# Strain_In.net
KiCad netlist of a schematic drawn in Altium Designer
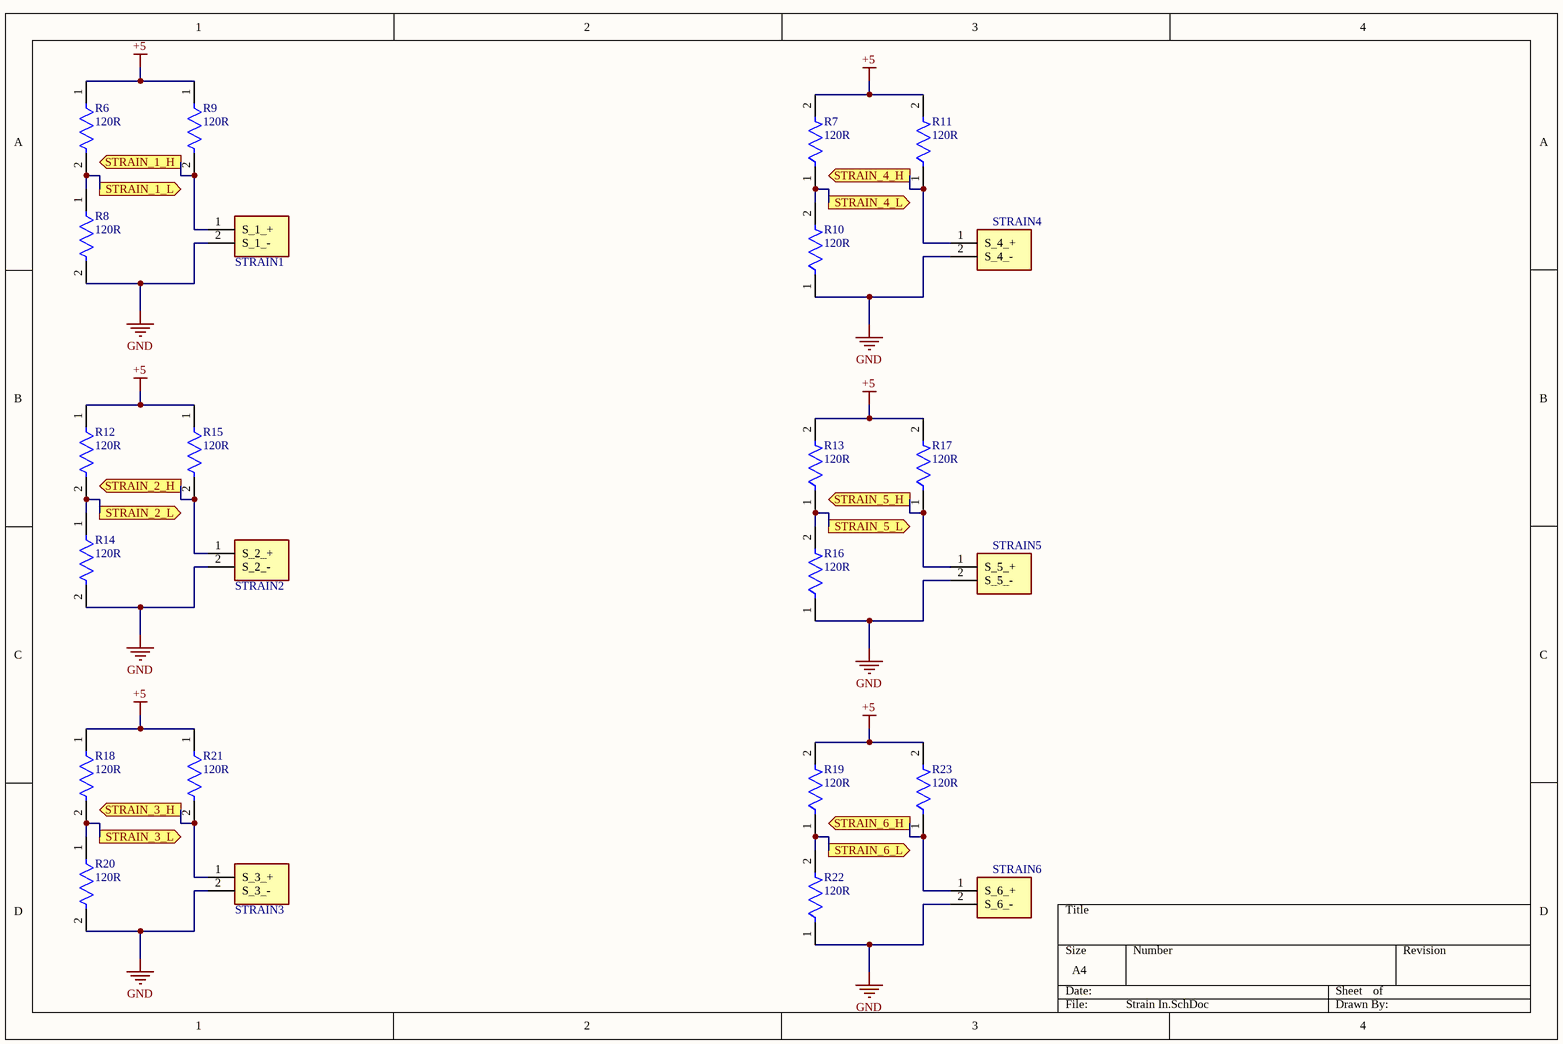
[diagram p0: Strain In.SchDoc]

(export (version "E")
  (design (tool "Eeschema 10.0.6"))
  (components
    (comp (ref "R6")
      (value "120R")
      (footprint "FP-CRCW1206-e3-MFG")
      (description "RES Thick Film, 120Ω, 1%, 0.25W, 100ppm/°C, 1206")
      (fields (field (name "TOLERANCE") "1%"))
      (libsource (lib "Altium Content Vault") (part "1029c3af85768c4190bb7ad29bc67b5"))
    )
    (comp (ref "R7")
      (value "120R")
      (footprint "FP-CRCW1206-e3-MFG")
      (description "RES Thick Film, 120Ω, 1%, 0.25W, 100ppm/°C, 1206")
      (fields (field (name "TOLERANCE") "1%"))
      (libsource (lib "Altium Content Vault") (part "1029c3af85768c4190bb7ad29bc67b5"))
    )
    (comp (ref "R8")
      (value "120R")
      (footprint "FP-CRCW1206-e3-MFG")
      (description "RES Thick Film, 120Ω, 1%, 0.25W, 100ppm/°C, 1206")
      (fields (field (name "TOLERANCE") "1%"))
      (libsource (lib "Altium Content Vault") (part "1029c3af85768c4190bb7ad29bc67b5"))
    )
    (comp (ref "R9")
      (value "120R")
      (footprint "FP-CRCW1206-e3-MFG")
      (description "RES Thick Film, 120Ω, 1%, 0.25W, 100ppm/°C, 1206")
      (fields (field (name "TOLERANCE") "1%"))
      (libsource (lib "Altium Content Vault") (part "1029c3af85768c4190bb7ad29bc67b5"))
    )
    (comp (ref "R10")
      (value "120R")
      (footprint "FP-CRCW1206-e3-MFG")
      (description "RES Thick Film, 120Ω, 1%, 0.25W, 100ppm/°C, 1206")
      (fields (field (name "TOLERANCE") "1%"))
      (libsource (lib "Altium Content Vault") (part "1029c3af85768c4190bb7ad29bc67b5"))
    )
    (comp (ref "R11")
      (value "120R")
      (footprint "FP-CRCW1206-e3-MFG")
      (description "RES Thick Film, 120Ω, 1%, 0.25W, 100ppm/°C, 1206")
      (fields (field (name "TOLERANCE") "1%"))
      (libsource (lib "Altium Content Vault") (part "1029c3af85768c4190bb7ad29bc67b5"))
    )
    (comp (ref "R12")
      (value "120R")
      (footprint "FP-CRCW1206-e3-MFG")
      (description "RES Thick Film, 120Ω, 1%, 0.25W, 100ppm/°C, 1206")
      (fields (field (name "TOLERANCE") "1%"))
      (libsource (lib "Altium Content Vault") (part "1029c3af85768c4190bb7ad29bc67b5"))
    )
    (comp (ref "R13")
      (value "120R")
      (footprint "FP-CRCW1206-e3-MFG")
      (description "RES Thick Film, 120Ω, 1%, 0.25W, 100ppm/°C, 1206")
      (fields (field (name "TOLERANCE") "1%"))
      (libsource (lib "Altium Content Vault") (part "1029c3af85768c4190bb7ad29bc67b5"))
    )
    (comp (ref "R14")
      (value "120R")
      (footprint "FP-CRCW1206-e3-MFG")
      (description "RES Thick Film, 120Ω, 1%, 0.25W, 100ppm/°C, 1206")
      (fields (field (name "TOLERANCE") "1%"))
      (libsource (lib "Altium Content Vault") (part "1029c3af85768c4190bb7ad29bc67b5"))
    )
    (comp (ref "R15")
      (value "120R")
      (footprint "FP-CRCW1206-e3-MFG")
      (description "RES Thick Film, 120Ω, 1%, 0.25W, 100ppm/°C, 1206")
      (fields (field (name "TOLERANCE") "1%"))
      (libsource (lib "Altium Content Vault") (part "1029c3af85768c4190bb7ad29bc67b5"))
    )
    (comp (ref "R16")
      (value "120R")
      (footprint "FP-CRCW1206-e3-MFG")
      (description "RES Thick Film, 120Ω, 1%, 0.25W, 100ppm/°C, 1206")
      (fields (field (name "TOLERANCE") "1%"))
      (libsource (lib "Altium Content Vault") (part "1029c3af85768c4190bb7ad29bc67b5"))
    )
    (comp (ref "R17")
      (value "120R")
      (footprint "FP-CRCW1206-e3-MFG")
      (description "RES Thick Film, 120Ω, 1%, 0.25W, 100ppm/°C, 1206")
      (fields (field (name "TOLERANCE") "1%"))
      (libsource (lib "Altium Content Vault") (part "1029c3af85768c4190bb7ad29bc67b5"))
    )
    (comp (ref "R18")
      (value "120R")
      (footprint "FP-CRCW1206-e3-MFG")
      (description "RES Thick Film, 120Ω, 1%, 0.25W, 100ppm/°C, 1206")
      (fields (field (name "TOLERANCE") "1%"))
      (libsource (lib "Altium Content Vault") (part "1029c3af85768c4190bb7ad29bc67b5"))
    )
    (comp (ref "R19")
      (value "120R")
      (footprint "FP-CRCW1206-e3-MFG")
      (description "RES Thick Film, 120Ω, 1%, 0.25W, 100ppm/°C, 1206")
      (fields (field (name "TOLERANCE") "1%"))
      (libsource (lib "Altium Content Vault") (part "1029c3af85768c4190bb7ad29bc67b5"))
    )
    (comp (ref "R20")
      (value "120R")
      (footprint "FP-CRCW1206-e3-MFG")
      (description "RES Thick Film, 120Ω, 1%, 0.25W, 100ppm/°C, 1206")
      (fields (field (name "TOLERANCE") "1%"))
      (libsource (lib "Altium Content Vault") (part "1029c3af85768c4190bb7ad29bc67b5"))
    )
    (comp (ref "R21")
      (value "120R")
      (footprint "FP-CRCW1206-e3-MFG")
      (description "RES Thick Film, 120Ω, 1%, 0.25W, 100ppm/°C, 1206")
      (fields (field (name "TOLERANCE") "1%"))
      (libsource (lib "Altium Content Vault") (part "1029c3af85768c4190bb7ad29bc67b5"))
    )
    (comp (ref "R22")
      (value "120R")
      (footprint "FP-CRCW1206-e3-MFG")
      (description "RES Thick Film, 120Ω, 1%, 0.25W, 100ppm/°C, 1206")
      (fields (field (name "TOLERANCE") "1%"))
      (libsource (lib "Altium Content Vault") (part "1029c3af85768c4190bb7ad29bc67b5"))
    )
    (comp (ref "R23")
      (value "120R")
      (footprint "FP-CRCW1206-e3-MFG")
      (description "RES Thick Film, 120Ω, 1%, 0.25W, 100ppm/°C, 1206")
      (fields (field (name "TOLERANCE") "1%"))
      (libsource (lib "Altium Content Vault") (part "1029c3af85768c4190bb7ad29bc67b5"))
    )
    (comp (ref "STRAIN1")
      (value "171971-0002")
      (footprint "SamacSys:SHDR2W65P0X254_1X2_738X510X1216P")
      (description "Connector")
      (fields (field (name "MOUSER2 PART NUMBER") "538-171971-0002"))
      (libsource (lib "SamacSys") (part "171971-0002"))
    )
    (comp (ref "STRAIN2")
      (value "171971-0002")
      (footprint "SamacSys:SHDR2W65P0X254_1X2_738X510X1216P")
      (description "Connector")
      (fields (field (name "MOUSER2 PART NUMBER") "538-171971-0002"))
      (libsource (lib "SamacSys") (part "171971-0002"))
    )
    (comp (ref "STRAIN3")
      (value "171971-0002")
      (footprint "SamacSys:SHDR2W65P0X254_1X2_738X510X1216P")
      (description "Connector")
      (fields (field (name "MOUSER2 PART NUMBER") "538-171971-0002"))
      (libsource (lib "SamacSys") (part "171971-0002"))
    )
    (comp (ref "STRAIN4")
      (value "171971-0002")
      (footprint "SamacSys:SHDR2W65P0X254_1X2_738X510X1216P")
      (description "Connector")
      (fields (field (name "MOUSER2 PART NUMBER") "538-171971-0002"))
      (libsource (lib "SamacSys") (part "171971-0002"))
    )
    (comp (ref "STRAIN5")
      (value "171971-0002")
      (footprint "SamacSys:SHDR2W65P0X254_1X2_738X510X1216P")
      (description "Connector")
      (fields (field (name "MOUSER2 PART NUMBER") "538-171971-0002"))
      (libsource (lib "SamacSys") (part "171971-0002"))
    )
    (comp (ref "STRAIN6")
      (value "171971-0002")
      (footprint "SamacSys:SHDR2W65P0X254_1X2_738X510X1216P")
      (description "Connector")
      (fields (field (name "MOUSER2 PART NUMBER") "538-171971-0002"))
      (libsource (lib "SamacSys") (part "171971-0002"))
    )
  )
  (nets
    (net (code "1") (name "+5") (class "Default")
      (node (ref "R11") (pin "2") (pinfunction "2_2") (pintype "passive"))
      (node (ref "R12") (pin "1") (pinfunction "1_1") (pintype "passive"))
      (node (ref "R13") (pin "2") (pinfunction "2_2") (pintype "passive"))
      (node (ref "R15") (pin "1") (pinfunction "1_1") (pintype "passive"))
      (node (ref "R17") (pin "2") (pinfunction "2_2") (pintype "passive"))
      (node (ref "R18") (pin "1") (pinfunction "1_1") (pintype "passive"))
      (node (ref "R19") (pin "2") (pinfunction "2_2") (pintype "passive"))
      (node (ref "R21") (pin "1") (pinfunction "1_1") (pintype "passive"))
      (node (ref "R23") (pin "2") (pinfunction "2_2") (pintype "passive"))
      (node (ref "R6") (pin "1") (pinfunction "1_1") (pintype "passive"))
      (node (ref "R7") (pin "2") (pinfunction "2_2") (pintype "passive"))
      (node (ref "R9") (pin "1") (pinfunction "1_1") (pintype "passive"))
    )
    (net (code "2") (name "/STRAIN_1_H") (class "Default")
      (node (ref "R9") (pin "2") (pinfunction "2_2") (pintype "passive"))
      (node (ref "STRAIN1") (pin "1") (pinfunction "S_1_+_1") (pintype "passive"))
    )
    (net (code "3") (name "/STRAIN_1_L") (class "Default")
      (node (ref "R6") (pin "2") (pinfunction "2_2") (pintype "passive"))
      (node (ref "R8") (pin "1") (pinfunction "1_1") (pintype "passive"))
    )
    (net (code "4") (name "/STRAIN_2_H") (class "Default")
      (node (ref "R15") (pin "2") (pinfunction "2_2") (pintype "passive"))
      (node (ref "STRAIN2") (pin "1") (pinfunction "S_1_+_1") (pintype "passive"))
    )
    (net (code "5") (name "/STRAIN_2_L") (class "Default")
      (node (ref "R12") (pin "2") (pinfunction "2_2") (pintype "passive"))
      (node (ref "R14") (pin "1") (pinfunction "1_1") (pintype "passive"))
    )
    (net (code "6") (name "/STRAIN_3_H") (class "Default")
      (node (ref "R21") (pin "2") (pinfunction "2_2") (pintype "passive"))
      (node (ref "STRAIN3") (pin "1") (pinfunction "S_1_+_1") (pintype "passive"))
    )
    (net (code "7") (name "/STRAIN_3_L") (class "Default")
      (node (ref "R18") (pin "2") (pinfunction "2_2") (pintype "passive"))
      (node (ref "R20") (pin "1") (pinfunction "1_1") (pintype "passive"))
    )
    (net (code "8") (name "/STRAIN_4_H") (class "Default")
      (node (ref "R11") (pin "1") (pinfunction "1_1") (pintype "passive"))
      (node (ref "STRAIN4") (pin "1") (pinfunction "S_1_+_1") (pintype "passive"))
    )
    (net (code "9") (name "/STRAIN_4_L") (class "Default")
      (node (ref "R10") (pin "2") (pinfunction "2_2") (pintype "passive"))
      (node (ref "R7") (pin "1") (pinfunction "1_1") (pintype "passive"))
    )
    (net (code "10") (name "/STRAIN_5_H") (class "Default")
      (node (ref "R17") (pin "1") (pinfunction "1_1") (pintype "passive"))
      (node (ref "STRAIN5") (pin "1") (pinfunction "S_1_+_1") (pintype "passive"))
    )
    (net (code "11") (name "/STRAIN_5_L") (class "Default")
      (node (ref "R13") (pin "1") (pinfunction "1_1") (pintype "passive"))
      (node (ref "R16") (pin "2") (pinfunction "2_2") (pintype "passive"))
    )
    (net (code "12") (name "/STRAIN_6_H") (class "Default")
      (node (ref "R23") (pin "1") (pinfunction "1_1") (pintype "passive"))
      (node (ref "STRAIN6") (pin "1") (pinfunction "S_1_+_1") (pintype "passive"))
    )
    (net (code "13") (name "/STRAIN_6_L") (class "Default")
      (node (ref "R19") (pin "1") (pinfunction "1_1") (pintype "passive"))
      (node (ref "R22") (pin "2") (pinfunction "2_2") (pintype "passive"))
    )
    (net (code "14") (name "GND") (class "Default")
      (node (ref "R10") (pin "1") (pinfunction "1_1") (pintype "passive"))
      (node (ref "R14") (pin "2") (pinfunction "2_2") (pintype "passive"))
      (node (ref "R16") (pin "1") (pinfunction "1_1") (pintype "passive"))
      (node (ref "R20") (pin "2") (pinfunction "2_2") (pintype "passive"))
      (node (ref "R22") (pin "1") (pinfunction "1_1") (pintype "passive"))
      (node (ref "R8") (pin "2") (pinfunction "2_2") (pintype "passive"))
      (node (ref "STRAIN1") (pin "2") (pinfunction "S_1_-_2") (pintype "passive"))
      (node (ref "STRAIN2") (pin "2") (pinfunction "S_1_-_2") (pintype "passive"))
      (node (ref "STRAIN3") (pin "2") (pinfunction "S_1_-_2") (pintype "passive"))
      (node (ref "STRAIN4") (pin "2") (pinfunction "S_1_-_2") (pintype "passive"))
      (node (ref "STRAIN5") (pin "2") (pinfunction "S_1_-_2") (pintype "passive"))
      (node (ref "STRAIN6") (pin "2") (pinfunction "S_1_-_2") (pintype "passive"))
    )
  )
)
